# Pg1_Microcontroller.net
KiCad netlist of a schematic drawn in Altium Designer
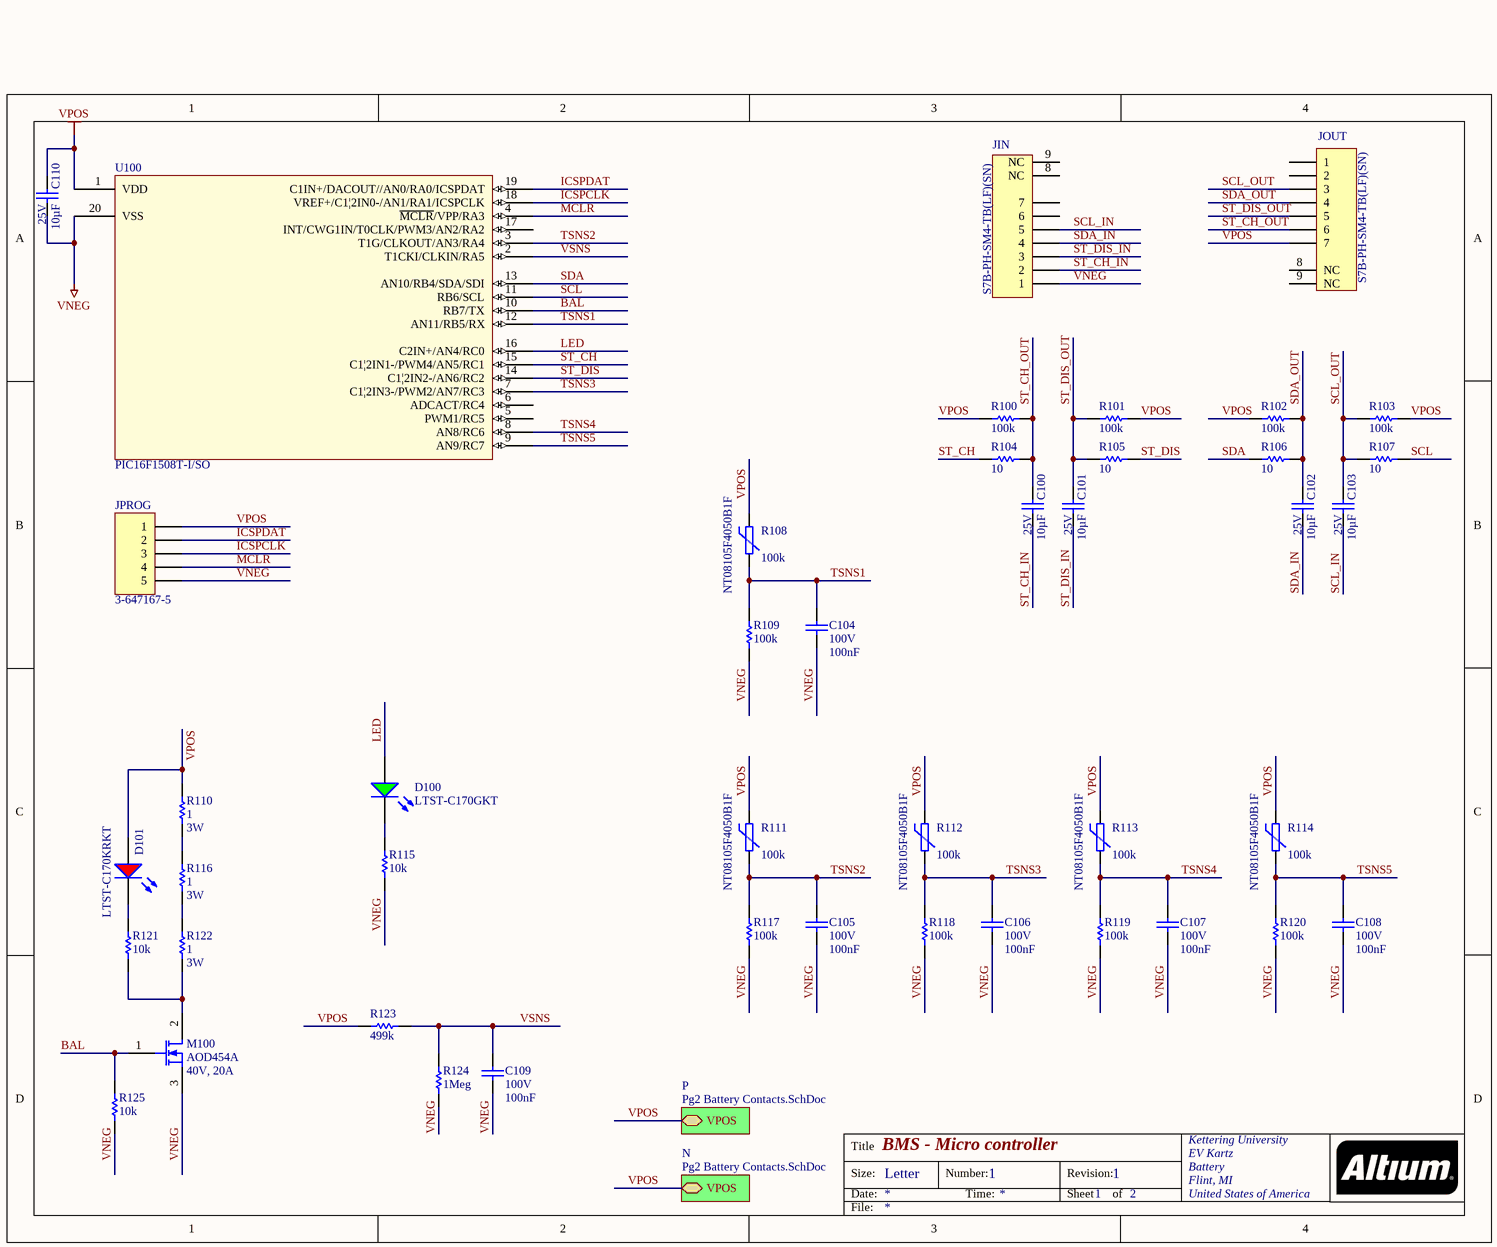
[diagram p0: Pg1_Microcontroller.SchDoc]

(export (version "E")
  (design (tool "Eeschema 10.0.6"))
  (components
    (comp (ref "C100")
      (value "10µF")
      (footprint "CAPC3225N")
      (description "Capacitor, Ceramic, 10µF, 25V, 0805, 10%, 125C")
      (fields (field (name "RATED") "25V") (field (name "Comment") "C1210C106K3RACAUTO"))
      (libsource (lib "SchLib - EE391 Master") (part "C1210C106K3RACAUTO"))
    )
    (comp (ref "C101")
      (value "10µF")
      (footprint "CAPC3225N")
      (description "Capacitor, Ceramic, 10µF, 25V, 0805, 10%, 125C")
      (fields (field (name "RATED") "25V") (field (name "Comment") "C1210C106K3RACAUTO"))
      (libsource (lib "SchLib - EE391 Master") (part "C1210C106K3RACAUTO"))
    )
    (comp (ref "C102")
      (value "10µF")
      (footprint "CAPC3225N")
      (description "Capacitor, Ceramic, 10µF, 25V, 0805, 10%, 125C")
      (fields (field (name "RATED") "25V") (field (name "Comment") "C1210C106K3RACAUTO"))
      (libsource (lib "SchLib - EE391 Master") (part "C1210C106K3RACAUTO"))
    )
    (comp (ref "C103")
      (value "10µF")
      (footprint "CAPC3225N")
      (description "Capacitor, Ceramic, 10µF, 25V, 0805, 10%, 125C")
      (fields (field (name "RATED") "25V") (field (name "Comment") "C1210C106K3RACAUTO"))
      (libsource (lib "SchLib - EE391 Master") (part "C1210C106K3RACAUTO"))
    )
    (comp (ref "C104")
      (value "100nF")
      (footprint "CAPC2012N")
      (description "Capacitor, Ceramic, 100nF, 100V, 0805, 10%, 125C")
      (fields (field (name "RATED") "100V") (field (name "Comment") "C0805C104K1RACAUTO"))
      (libsource (lib "SchLib - EE391 Master") (part "C0805C104K1RACAUTO"))
    )
    (comp (ref "C105")
      (value "100nF")
      (footprint "CAPC2012N")
      (description "Capacitor, Ceramic, 100nF, 100V, 0805, 10%, 125C")
      (fields (field (name "RATED") "100V") (field (name "Comment") "C0805C104K1RACAUTO"))
      (libsource (lib "SchLib - EE391 Master") (part "C0805C104K1RACAUTO"))
    )
    (comp (ref "C106")
      (value "100nF")
      (footprint "CAPC2012N")
      (description "Capacitor, Ceramic, 100nF, 100V, 0805, 10%, 125C")
      (fields (field (name "RATED") "100V") (field (name "Comment") "C0805C104K1RACAUTO"))
      (libsource (lib "SchLib - EE391 Master") (part "C0805C104K1RACAUTO"))
    )
    (comp (ref "C107")
      (value "100nF")
      (footprint "CAPC2012N")
      (description "Capacitor, Ceramic, 100nF, 100V, 0805, 10%, 125C")
      (fields (field (name "RATED") "100V") (field (name "Comment") "C0805C104K1RACAUTO"))
      (libsource (lib "SchLib - EE391 Master") (part "C0805C104K1RACAUTO"))
    )
    (comp (ref "C108")
      (value "100nF")
      (footprint "CAPC2012N")
      (description "Capacitor, Ceramic, 100nF, 100V, 0805, 10%, 125C")
      (fields (field (name "RATED") "100V") (field (name "Comment") "C0805C104K1RACAUTO"))
      (libsource (lib "SchLib - EE391 Master") (part "C0805C104K1RACAUTO"))
    )
    (comp (ref "C109")
      (value "100nF")
      (footprint "CAPC2012N")
      (description "Capacitor, Ceramic, 100nF, 100V, 0805, 10%, 125C")
      (fields (field (name "RATED") "100V") (field (name "Comment") "C0805C104K1RACAUTO"))
      (libsource (lib "SchLib - EE391 Master") (part "C0805C104K1RACAUTO"))
    )
    (comp (ref "C110")
      (value "10µF")
      (footprint "CAPC3225N")
      (description "Capacitor, Ceramic, 10µF, 25V, 0805, 10%, 125C")
      (fields (field (name "RATED") "25V") (field (name "Comment") "C1210C106K3RACAUTO"))
      (libsource (lib "SchLib - EE391 Master") (part "C1210C106K3RACAUTO"))
    )
    (comp (ref "D100")
      (value "LTST-C170GKT")
      (footprint "DIO2012N-G")
      (description "LED, SMT 0805, Green, 2.1V, 10mA")
      (libsource (lib "SchLib - EE391 Master") (part "LTST-C170GKT"))
    )
    (comp (ref "D101")
      (value "LTST-C170KRKT")
      (footprint "DIO2012N-R")
      (description "LED, SMT 0805, Red, 2.0V, 20mA")
      (libsource (lib "SchLib - EE391 Master") (part "LTST-C170KRKT"))
    )
    (comp (ref "JIN")
      (value "S7B-PH-SM4-TB(LF)(SN)")
      (footprint "JST-PH-S7")
      (description "Header, JST, 7-Pin, Right-Angle, PH, Surface Mount")
      (libsource (lib "") (part "S7B-PH-SM4-TB(LF)(SN)_1"))
    )
    (comp (ref "JOUT")
      (value "S7B-PH-SM4-TB(LF)(SN)")
      (footprint "JST-PH-S7")
      (description "Header, JST, 7-Pin, Right-Angle, PH, Surface Mount")
      (libsource (lib "SchLib - EE391 Master") (part "S7B-PH-SM4-TB(LF)(SN)"))
    )
    (comp (ref "JPROG")
      (value "3-647167-5")
      (footprint "HDR1X5 SMT")
      (description "Header, 1x5-Pin, SMT, 100mil Pitch")
      (libsource (lib "SchLib - EE391 Master") (part "Hdr 3-647167-5"))
    )
    (comp (ref "M100")
      (value "AOD454A")
      (footprint "TO252-3N")
      (description "MOSFET, N-Ch, 40V, 20A, 430mOhm, TO252")
      (fields (field (name "RATED") "40V, 20A"))
      (libsource (lib "SchLib - EE391 Master") (part "AOD454A"))
    )
    (comp (ref "R100")
      (value "100k")
      (footprint "RESC2012N")
      (description "Resistor, Fixed, 100 kOhm, 0805, 1%, 1/8W")
      (fields (field (name "Comment") "ERJ-6ENF1003V"))
      (libsource (lib "SchLib - EE391 Master") (part "ERJ-6ENF1003V"))
    )
    (comp (ref "R101")
      (value "100k")
      (footprint "RESC2012N")
      (description "Resistor, Fixed, 100 kOhm, 0805, 1%, 1/8W")
      (fields (field (name "Comment") "ERJ-6ENF1003V"))
      (libsource (lib "SchLib - EE391 Master") (part "ERJ-6ENF1003V"))
    )
    (comp (ref "R102")
      (value "100k")
      (footprint "RESC2012N")
      (description "Resistor, Fixed, 100 kOhm, 0805, 1%, 1/8W")
      (fields (field (name "Comment") "ERJ-6ENF1003V"))
      (libsource (lib "SchLib - EE391 Master") (part "ERJ-6ENF1003V"))
    )
    (comp (ref "R103")
      (value "100k")
      (footprint "RESC2012N")
      (description "Resistor, Fixed, 100 kOhm, 0805, 1%, 1/8W")
      (fields (field (name "Comment") "ERJ-6ENF1003V"))
      (libsource (lib "SchLib - EE391 Master") (part "ERJ-6ENF1003V"))
    )
    (comp (ref "R104")
      (value "10")
      (footprint "RESC2012N")
      (description "Resistor, Fixed, 10 Ohm, 0805, 1%, 1/8W")
      (fields (field (name "Comment") "ERJ-6ENF10R0V"))
      (libsource (lib "SchLib - EE391 Master") (part "ERJ-6ENF10R0V"))
    )
    (comp (ref "R105")
      (value "10")
      (footprint "RESC2012N")
      (description "Resistor, Fixed, 10 Ohm, 0805, 1%, 1/8W")
      (fields (field (name "Comment") "ERJ-6ENF10R0V"))
      (libsource (lib "SchLib - EE391 Master") (part "ERJ-6ENF10R0V"))
    )
    (comp (ref "R106")
      (value "10")
      (footprint "RESC2012N")
      (description "Resistor, Fixed, 10 Ohm, 0805, 1%, 1/8W")
      (fields (field (name "Comment") "ERJ-6ENF10R0V"))
      (libsource (lib "SchLib - EE391 Master") (part "ERJ-6ENF10R0V"))
    )
    (comp (ref "R107")
      (value "10")
      (footprint "RESC2012N")
      (description "Resistor, Fixed, 10 Ohm, 0805, 1%, 1/8W")
      (fields (field (name "Comment") "ERJ-6ENF10R0V"))
      (libsource (lib "SchLib - EE391 Master") (part "ERJ-6ENF10R0V"))
    )
    (comp (ref "R108")
      (value "NT08105F4050B1F")
      (footprint "RESC2012N")
      (description "Resistor, NTC Thermistor, 100kOhm, 0805, 1%, 125C")
      (fields (field (name "ALTIUM_VALUE") "100k"))
      (libsource (lib "SchLib - EE391 Master") (part "NTCS0805E3103FMT"))
    )
    (comp (ref "R109")
      (value "100k")
      (footprint "RESC2012N")
      (description "Resistor, Fixed, 100 kOhm, 0805, 1%, 1/8W")
      (fields (field (name "Comment") "ERJ-6ENF1003V"))
      (libsource (lib "SchLib - EE391 Master") (part "ERJ-6ENF1003V"))
    )
    (comp (ref "R110")
      (value "1")
      (footprint "RESC6432N")
      (description "Resistor, Power, 1 Ohm, 6432, 5%, 3W")
      (fields (field (name "RATED") "3W") (field (name "Comment") "35221R0JT"))
      (libsource (lib "SchLib - EE391 Master") (part "35221R0JT"))
    )
    (comp (ref "R111")
      (value "NT08105F4050B1F")
      (footprint "RESC2012N")
      (description "Resistor, NTC Thermistor, 100kOhm, 0805, 1%, 125C")
      (fields (field (name "ALTIUM_VALUE") "100k"))
      (libsource (lib "SchLib - EE391 Master") (part "NTCS0805E3103FMT"))
    )
    (comp (ref "R112")
      (value "NT08105F4050B1F")
      (footprint "RESC2012N")
      (description "Resistor, NTC Thermistor, 100kOhm, 0805, 1%, 125C")
      (fields (field (name "ALTIUM_VALUE") "100k"))
      (libsource (lib "SchLib - EE391 Master") (part "NTCS0805E3103FMT"))
    )
    (comp (ref "R113")
      (value "NT08105F4050B1F")
      (footprint "RESC2012N")
      (description "Resistor, NTC Thermistor, 100kOhm, 0805, 1%, 125C")
      (fields (field (name "ALTIUM_VALUE") "100k"))
      (libsource (lib "SchLib - EE391 Master") (part "NTCS0805E3103FMT"))
    )
    (comp (ref "R114")
      (value "NT08105F4050B1F")
      (footprint "RESC2012N")
      (description "Resistor, NTC Thermistor, 100kOhm, 0805, 1%, 125C")
      (fields (field (name "ALTIUM_VALUE") "100k"))
      (libsource (lib "SchLib - EE391 Master") (part "NTCS0805E3103FMT"))
    )
    (comp (ref "R115")
      (value "10k")
      (footprint "RESC2012N")
      (description "Resistor, Fixed, 10 kOhm, 0805, 1%, 1/8W")
      (fields (field (name "Comment") "ERJ-6ENF1002V"))
      (libsource (lib "SchLib - EE391 Master") (part "ERJ-6ENF1002V"))
    )
    (comp (ref "R116")
      (value "1")
      (footprint "RESC6432N")
      (description "Resistor, Power, 1 Ohm, 6432, 5%, 3W")
      (fields (field (name "RATED") "3W") (field (name "Comment") "35221R0JT"))
      (libsource (lib "SchLib - EE391 Master") (part "35221R0JT"))
    )
    (comp (ref "R117")
      (value "100k")
      (footprint "RESC2012N")
      (description "Resistor, Fixed, 100 kOhm, 0805, 1%, 1/8W")
      (fields (field (name "Comment") "ERJ-6ENF1003V"))
      (libsource (lib "SchLib - EE391 Master") (part "ERJ-6ENF1003V"))
    )
    (comp (ref "R118")
      (value "100k")
      (footprint "RESC2012N")
      (description "Resistor, Fixed, 100 kOhm, 0805, 1%, 1/8W")
      (fields (field (name "Comment") "ERJ-6ENF1003V"))
      (libsource (lib "SchLib - EE391 Master") (part "ERJ-6ENF1003V"))
    )
    (comp (ref "R119")
      (value "100k")
      (footprint "RESC2012N")
      (description "Resistor, Fixed, 100 kOhm, 0805, 1%, 1/8W")
      (fields (field (name "Comment") "ERJ-6ENF1003V"))
      (libsource (lib "SchLib - EE391 Master") (part "ERJ-6ENF1003V"))
    )
    (comp (ref "R120")
      (value "100k")
      (footprint "RESC2012N")
      (description "Resistor, Fixed, 100 kOhm, 0805, 1%, 1/8W")
      (fields (field (name "Comment") "ERJ-6ENF1003V"))
      (libsource (lib "SchLib - EE391 Master") (part "ERJ-6ENF1003V"))
    )
    (comp (ref "R121")
      (value "10k")
      (footprint "RESC2012N")
      (description "Resistor, Fixed, 10 kOhm, 0805, 1%, 1/8W")
      (fields (field (name "Comment") "ERJ-6ENF1002V"))
      (libsource (lib "SchLib - EE391 Master") (part "ERJ-6ENF1002V"))
    )
    (comp (ref "R122")
      (value "1")
      (footprint "RESC6432N")
      (description "Resistor, Power, 1 Ohm, 6432, 5%, 3W")
      (fields (field (name "RATED") "3W") (field (name "Comment") "35221R0JT"))
      (libsource (lib "SchLib - EE391 Master") (part "35221R0JT"))
    )
    (comp (ref "R123")
      (value "499k")
      (footprint "RESC2012N")
      (description "Resistor, Fixed, 499 kOhm, 0805, 1%, 1/8W")
      (fields (field (name "Comment") "ERJ-6ENF4993V"))
      (libsource (lib "SchLib - EE391 Master") (part "ERJ-6ENF4993V"))
    )
    (comp (ref "R124")
      (value "1Meg")
      (footprint "RESC2012N")
      (description "Resistor, Fixed, 1 MOhm, 0805, 1%, 1/8W")
      (fields (field (name "Comment") "ERJ-6ENF1004V"))
      (libsource (lib "SchLib - EE391 Master") (part "ERJ-6ENF1004V"))
    )
    (comp (ref "R125")
      (value "10k")
      (footprint "RESC2012N")
      (description "Resistor, Fixed, 10 kOhm, 0805, 1%, 1/8W")
      (fields (field (name "Comment") "ERJ-6ENF1002V"))
      (libsource (lib "SchLib - EE391 Master") (part "ERJ-6ENF1002V"))
    )
    (comp (ref "U100")
      (value "PIC16F1508T-I/SO")
      (footprint "SOIC-20-300")
      (description "MCU, 8-Bit, 5V, 32MHz, 20-Pin SOIC")
      (libsource (lib "SchLib - EE391 Master") (part "PIC16F1508T-I/SO"))
    )
  )
  (nets
    (net (code "1") (name "/BAL") (class "Default")
      (node (ref "M100") (pin "1") (pinfunction "G_1") (pintype "passive"))
      (node (ref "R125") (pin "2") (pinfunction "2_2") (pintype "passive"))
      (node (ref "U100") (pin "10") (pinfunction "RB7/TX_10") (pintype "bidirectional"))
    )
    (net (code "2") (name "/ICSPCLK") (class "Default")
      (node (ref "JPROG") (pin "3") (pinfunction "3_3") (pintype "passive"))
      (node (ref "U100") (pin "18") (pinfunction "VREF+/C1¦2IN0-/AN1/RA1/ICSPCLK_18") (pintype "bidirectional"))
    )
    (net (code "3") (name "/ICSPDAT") (class "Default")
      (node (ref "JPROG") (pin "2") (pinfunction "2_2") (pintype "passive"))
      (node (ref "U100") (pin "19") (pinfunction "C1IN+/DACOUT//AN0/RA0/ICSPDAT_19") (pintype "bidirectional"))
    )
    (net (code "4") (name "/LED") (class "Default")
      (node (ref "D100") (pin "1") (pinfunction "A_1") (pintype "passive"))
      (node (ref "U100") (pin "16") (pinfunction "C2IN+/AN4/RC0_16") (pintype "bidirectional"))
    )
    (net (code "5") (name "/MCLR") (class "Default")
      (node (ref "JPROG") (pin "4") (pinfunction "4_4") (pintype "passive"))
      (node (ref "U100") (pin "4") (pinfunction "~{MCLR}/VPP/RA3_4") (pintype "bidirectional"))
    )
    (net (code "6") (name "/SCL") (class "Default")
      (node (ref "R107") (pin "2") (pinfunction "2_2") (pintype "passive"))
      (node (ref "U100") (pin "11") (pinfunction "RB6/SCL_11") (pintype "bidirectional"))
    )
    (net (code "7") (name "/SCL_IN") (class "Default")
      (node (ref "C103") (pin "1") (pinfunction "1_1") (pintype "passive"))
      (node (ref "JIN") (pin "5") (pinfunction "5_5") (pintype "passive"))
    )
    (net (code "8") (name "/SCL_OUT") (class "Default")
      (node (ref "C103") (pin "2") (pinfunction "2_2") (pintype "passive"))
      (node (ref "JOUT") (pin "3") (pinfunction "3_3") (pintype "passive"))
      (node (ref "R103") (pin "2") (pinfunction "2_2") (pintype "passive"))
      (node (ref "R107") (pin "1") (pinfunction "1_1") (pintype "passive"))
    )
    (net (code "9") (name "/SDA") (class "Default")
      (node (ref "R106") (pin "1") (pinfunction "1_1") (pintype "passive"))
      (node (ref "U100") (pin "13") (pinfunction "AN10/RB4/SDA/SDI_13") (pintype "bidirectional"))
    )
    (net (code "10") (name "/SDA_IN") (class "Default")
      (node (ref "C102") (pin "1") (pinfunction "1_1") (pintype "passive"))
      (node (ref "JIN") (pin "4") (pinfunction "4_4") (pintype "passive"))
    )
    (net (code "11") (name "/SDA_OUT") (class "Default")
      (node (ref "C102") (pin "2") (pinfunction "2_2") (pintype "passive"))
      (node (ref "JOUT") (pin "4") (pinfunction "4_4") (pintype "passive"))
      (node (ref "R102") (pin "1") (pinfunction "1_1") (pintype "passive"))
      (node (ref "R106") (pin "2") (pinfunction "2_2") (pintype "passive"))
    )
    (net (code "12") (name "/ST_CH") (class "Default")
      (node (ref "R104") (pin "1") (pinfunction "1_1") (pintype "passive"))
      (node (ref "U100") (pin "15") (pinfunction "C1¦2IN1-/PWM4/AN5/RC1_15") (pintype "bidirectional"))
    )
    (net (code "13") (name "/ST_CH_IN") (class "Default")
      (node (ref "C100") (pin "1") (pinfunction "1_1") (pintype "passive"))
      (node (ref "JIN") (pin "2") (pinfunction "2_2") (pintype "passive"))
    )
    (net (code "14") (name "/ST_CH_OUT") (class "Default")
      (node (ref "C100") (pin "2") (pinfunction "2_2") (pintype "passive"))
      (node (ref "JOUT") (pin "6") (pinfunction "6_6") (pintype "passive"))
      (node (ref "R100") (pin "1") (pinfunction "1_1") (pintype "passive"))
      (node (ref "R104") (pin "2") (pinfunction "2_2") (pintype "passive"))
    )
    (net (code "15") (name "/ST_DIS") (class "Default")
      (node (ref "R105") (pin "2") (pinfunction "2_2") (pintype "passive"))
      (node (ref "U100") (pin "14") (pinfunction "C1¦2IN2-/AN6/RC2_14") (pintype "bidirectional"))
    )
    (net (code "16") (name "/ST_DIS_IN") (class "Default")
      (node (ref "C101") (pin "1") (pinfunction "1_1") (pintype "passive"))
      (node (ref "JIN") (pin "3") (pinfunction "3_3") (pintype "passive"))
    )
    (net (code "17") (name "/ST_DIS_OUT") (class "Default")
      (node (ref "C101") (pin "2") (pinfunction "2_2") (pintype "passive"))
      (node (ref "JOUT") (pin "5") (pinfunction "5_5") (pintype "passive"))
      (node (ref "R101") (pin "2") (pinfunction "2_2") (pintype "passive"))
      (node (ref "R105") (pin "1") (pinfunction "1_1") (pintype "passive"))
    )
    (net (code "18") (name "/TSNS1") (class "Default")
      (node (ref "C104") (pin "1") (pinfunction "1_1") (pintype "passive"))
      (node (ref "R108") (pin "2") (pinfunction "2_2") (pintype "passive"))
      (node (ref "R109") (pin "2") (pinfunction "2_2") (pintype "passive"))
      (node (ref "U100") (pin "12") (pinfunction "AN11/RB5/RX_12") (pintype "bidirectional"))
    )
    (net (code "19") (name "/TSNS2") (class "Default")
      (node (ref "C105") (pin "1") (pinfunction "1_1") (pintype "passive"))
      (node (ref "R111") (pin "2") (pinfunction "2_2") (pintype "passive"))
      (node (ref "R117") (pin "2") (pinfunction "2_2") (pintype "passive"))
      (node (ref "U100") (pin "3") (pinfunction "T1G/CLKOUT/AN3/RA4_3") (pintype "bidirectional"))
    )
    (net (code "20") (name "/TSNS3") (class "Default")
      (node (ref "C106") (pin "1") (pinfunction "1_1") (pintype "passive"))
      (node (ref "R112") (pin "2") (pinfunction "2_2") (pintype "passive"))
      (node (ref "R118") (pin "2") (pinfunction "2_2") (pintype "passive"))
      (node (ref "U100") (pin "7") (pinfunction "C1¦2IN3-/PWM2/AN7/RC3_7") (pintype "bidirectional"))
    )
    (net (code "21") (name "/TSNS4") (class "Default")
      (node (ref "C107") (pin "1") (pinfunction "1_1") (pintype "passive"))
      (node (ref "R113") (pin "2") (pinfunction "2_2") (pintype "passive"))
      (node (ref "R119") (pin "2") (pinfunction "2_2") (pintype "passive"))
      (node (ref "U100") (pin "8") (pinfunction "AN8/RC6_8") (pintype "bidirectional"))
    )
    (net (code "22") (name "/TSNS5") (class "Default")
      (node (ref "C108") (pin "1") (pinfunction "1_1") (pintype "passive"))
      (node (ref "R114") (pin "2") (pinfunction "2_2") (pintype "passive"))
      (node (ref "R120") (pin "2") (pinfunction "2_2") (pintype "passive"))
      (node (ref "U100") (pin "9") (pinfunction "AN9/RC7_9") (pintype "bidirectional"))
    )
    (net (code "23") (name "/VSNS") (class "Default")
      (node (ref "C109") (pin "1") (pinfunction "1_1") (pintype "passive"))
      (node (ref "R123") (pin "1") (pinfunction "1_1") (pintype "passive"))
      (node (ref "R124") (pin "2") (pinfunction "2_2") (pintype "passive"))
      (node (ref "U100") (pin "2") (pinfunction "T1CKI/CLKIN/RA5_2") (pintype "bidirectional"))
    )
    (net (code "24") (name "Net-(D100-K)") (class "Default")
      (node (ref "D100") (pin "2") (pinfunction "K_2") (pintype "passive"))
      (node (ref "R115") (pin "2") (pinfunction "2_2") (pintype "passive"))
    )
    (net (code "25") (name "Net-(D101-K)") (class "Default")
      (node (ref "D101") (pin "2") (pinfunction "K_2") (pintype "passive"))
      (node (ref "R121") (pin "2") (pinfunction "2_2") (pintype "passive"))
    )
    (net (code "26") (name "Net-(M100-D)") (class "Default")
      (node (ref "M100") (pin "2") (pinfunction "D_2") (pintype "passive"))
      (node (ref "R121") (pin "1") (pinfunction "1_1") (pintype "passive"))
      (node (ref "R122") (pin "1") (pinfunction "1_1") (pintype "passive"))
    )
    (net (code "27") (name "Net-(R110-Pad1)") (class "Default")
      (node (ref "R110") (pin "1") (pinfunction "1_1") (pintype "passive"))
      (node (ref "R116") (pin "2") (pinfunction "2_2") (pintype "passive"))
    )
    (net (code "28") (name "Net-(R116-Pad1)") (class "Default")
      (node (ref "R116") (pin "1") (pinfunction "1_1") (pintype "passive"))
      (node (ref "R122") (pin "2") (pinfunction "2_2") (pintype "passive"))
    )
    (net (code "29") (name "VNEG") (class "Default")
      (node (ref "C104") (pin "2") (pinfunction "2_2") (pintype "passive"))
      (node (ref "C105") (pin "2") (pinfunction "2_2") (pintype "passive"))
      (node (ref "C106") (pin "2") (pinfunction "2_2") (pintype "passive"))
      (node (ref "C107") (pin "2") (pinfunction "2_2") (pintype "passive"))
      (node (ref "C108") (pin "2") (pinfunction "2_2") (pintype "passive"))
      (node (ref "C109") (pin "2") (pinfunction "2_2") (pintype "passive"))
      (node (ref "C110") (pin "1") (pinfunction "1_1") (pintype "passive"))
      (node (ref "JIN") (pin "1") (pinfunction "1_1") (pintype "passive"))
      (node (ref "JPROG") (pin "5") (pinfunction "5_5") (pintype "passive"))
      (node (ref "M100") (pin "3") (pinfunction "S_3") (pintype "passive"))
      (node (ref "R109") (pin "1") (pinfunction "1_1") (pintype "passive"))
      (node (ref "R115") (pin "1") (pinfunction "1_1") (pintype "passive"))
      (node (ref "R117") (pin "1") (pinfunction "1_1") (pintype "passive"))
      (node (ref "R118") (pin "1") (pinfunction "1_1") (pintype "passive"))
      (node (ref "R119") (pin "1") (pinfunction "1_1") (pintype "passive"))
      (node (ref "R120") (pin "1") (pinfunction "1_1") (pintype "passive"))
      (node (ref "R124") (pin "1") (pinfunction "1_1") (pintype "passive"))
      (node (ref "R125") (pin "1") (pinfunction "1_1") (pintype "passive"))
      (node (ref "U100") (pin "20") (pinfunction "VSS_20") (pintype "power_in"))
    )
    (net (code "30") (name "VPOS") (class "Default")
      (node (ref "C110") (pin "2") (pinfunction "2_2") (pintype "passive"))
      (node (ref "D101") (pin "1") (pinfunction "A_1") (pintype "passive"))
      (node (ref "JOUT") (pin "7") (pinfunction "7_7") (pintype "passive"))
      (node (ref "JPROG") (pin "1") (pinfunction "1_1") (pintype "passive"))
      (node (ref "R100") (pin "2") (pinfunction "2_2") (pintype "passive"))
      (node (ref "R101") (pin "1") (pinfunction "1_1") (pintype "passive"))
      (node (ref "R102") (pin "2") (pinfunction "2_2") (pintype "passive"))
      (node (ref "R103") (pin "1") (pinfunction "1_1") (pintype "passive"))
      (node (ref "R108") (pin "1") (pinfunction "1_1") (pintype "passive"))
      (node (ref "R110") (pin "2") (pinfunction "2_2") (pintype "passive"))
      (node (ref "R111") (pin "1") (pinfunction "1_1") (pintype "passive"))
      (node (ref "R112") (pin "1") (pinfunction "1_1") (pintype "passive"))
      (node (ref "R113") (pin "1") (pinfunction "1_1") (pintype "passive"))
      (node (ref "R114") (pin "1") (pinfunction "1_1") (pintype "passive"))
      (node (ref "R123") (pin "2") (pinfunction "2_2") (pintype "passive"))
      (node (ref "U100") (pin "1") (pinfunction "VDD_1") (pintype "power_in"))
    )
    (net (code "31") (name "unconnected-(JIN-NC-Pad8)") (class "Default")
      (node (ref "JIN") (pin "8") (pinfunction "NC_8") (pintype "tri_state"))
    )
    (net (code "32") (name "unconnected-(JIN-NC-Pad9)") (class "Default")
      (node (ref "JIN") (pin "9") (pinfunction "NC_9") (pintype "tri_state"))
    )
    (net (code "33") (name "unconnected-(JIN-Pad6)") (class "Default")
      (node (ref "JIN") (pin "6") (pinfunction "6_6") (pintype "passive"))
    )
    (net (code "34") (name "unconnected-(JIN-Pad7)") (class "Default")
      (node (ref "JIN") (pin "7") (pinfunction "7_7") (pintype "passive"))
    )
    (net (code "35") (name "unconnected-(JOUT-NC-Pad8)") (class "Default")
      (node (ref "JOUT") (pin "8") (pinfunction "NC_8") (pintype "tri_state"))
    )
    (net (code "36") (name "unconnected-(JOUT-NC-Pad9)") (class "Default")
      (node (ref "JOUT") (pin "9") (pinfunction "NC_9") (pintype "tri_state"))
    )
    (net (code "37") (name "unconnected-(JOUT-Pad1)") (class "Default")
      (node (ref "JOUT") (pin "1") (pinfunction "1_1") (pintype "passive"))
    )
    (net (code "38") (name "unconnected-(JOUT-Pad2)") (class "Default")
      (node (ref "JOUT") (pin "2") (pinfunction "2_2") (pintype "passive"))
    )
    (net (code "39") (name "unconnected-(U100-ADCACT{slash}RC4-Pad6)") (class "Default")
      (node (ref "U100") (pin "6") (pinfunction "ADCACT/RC4_6") (pintype "bidirectional"))
    )
    (net (code "40") (name "unconnected-(U100-INT{slash}CWG1IN{slash}T0CLK{slash}PWM3{slash}AN2{slash}RA2-Pad17)") (class "Default")
      (node (ref "U100") (pin "17") (pinfunction "INT/CWG1IN/T0CLK/PWM3/AN2/RA2_17") (pintype "bidirectional"))
    )
    (net (code "41") (name "unconnected-(U100-PWM1{slash}RC5-Pad5)") (class "Default")
      (node (ref "U100") (pin "5") (pinfunction "PWM1/RC5_5") (pintype "bidirectional"))
    )
  )
)
